# talkbit.net
KiCad netlist of a schematic drawn in EAGLE
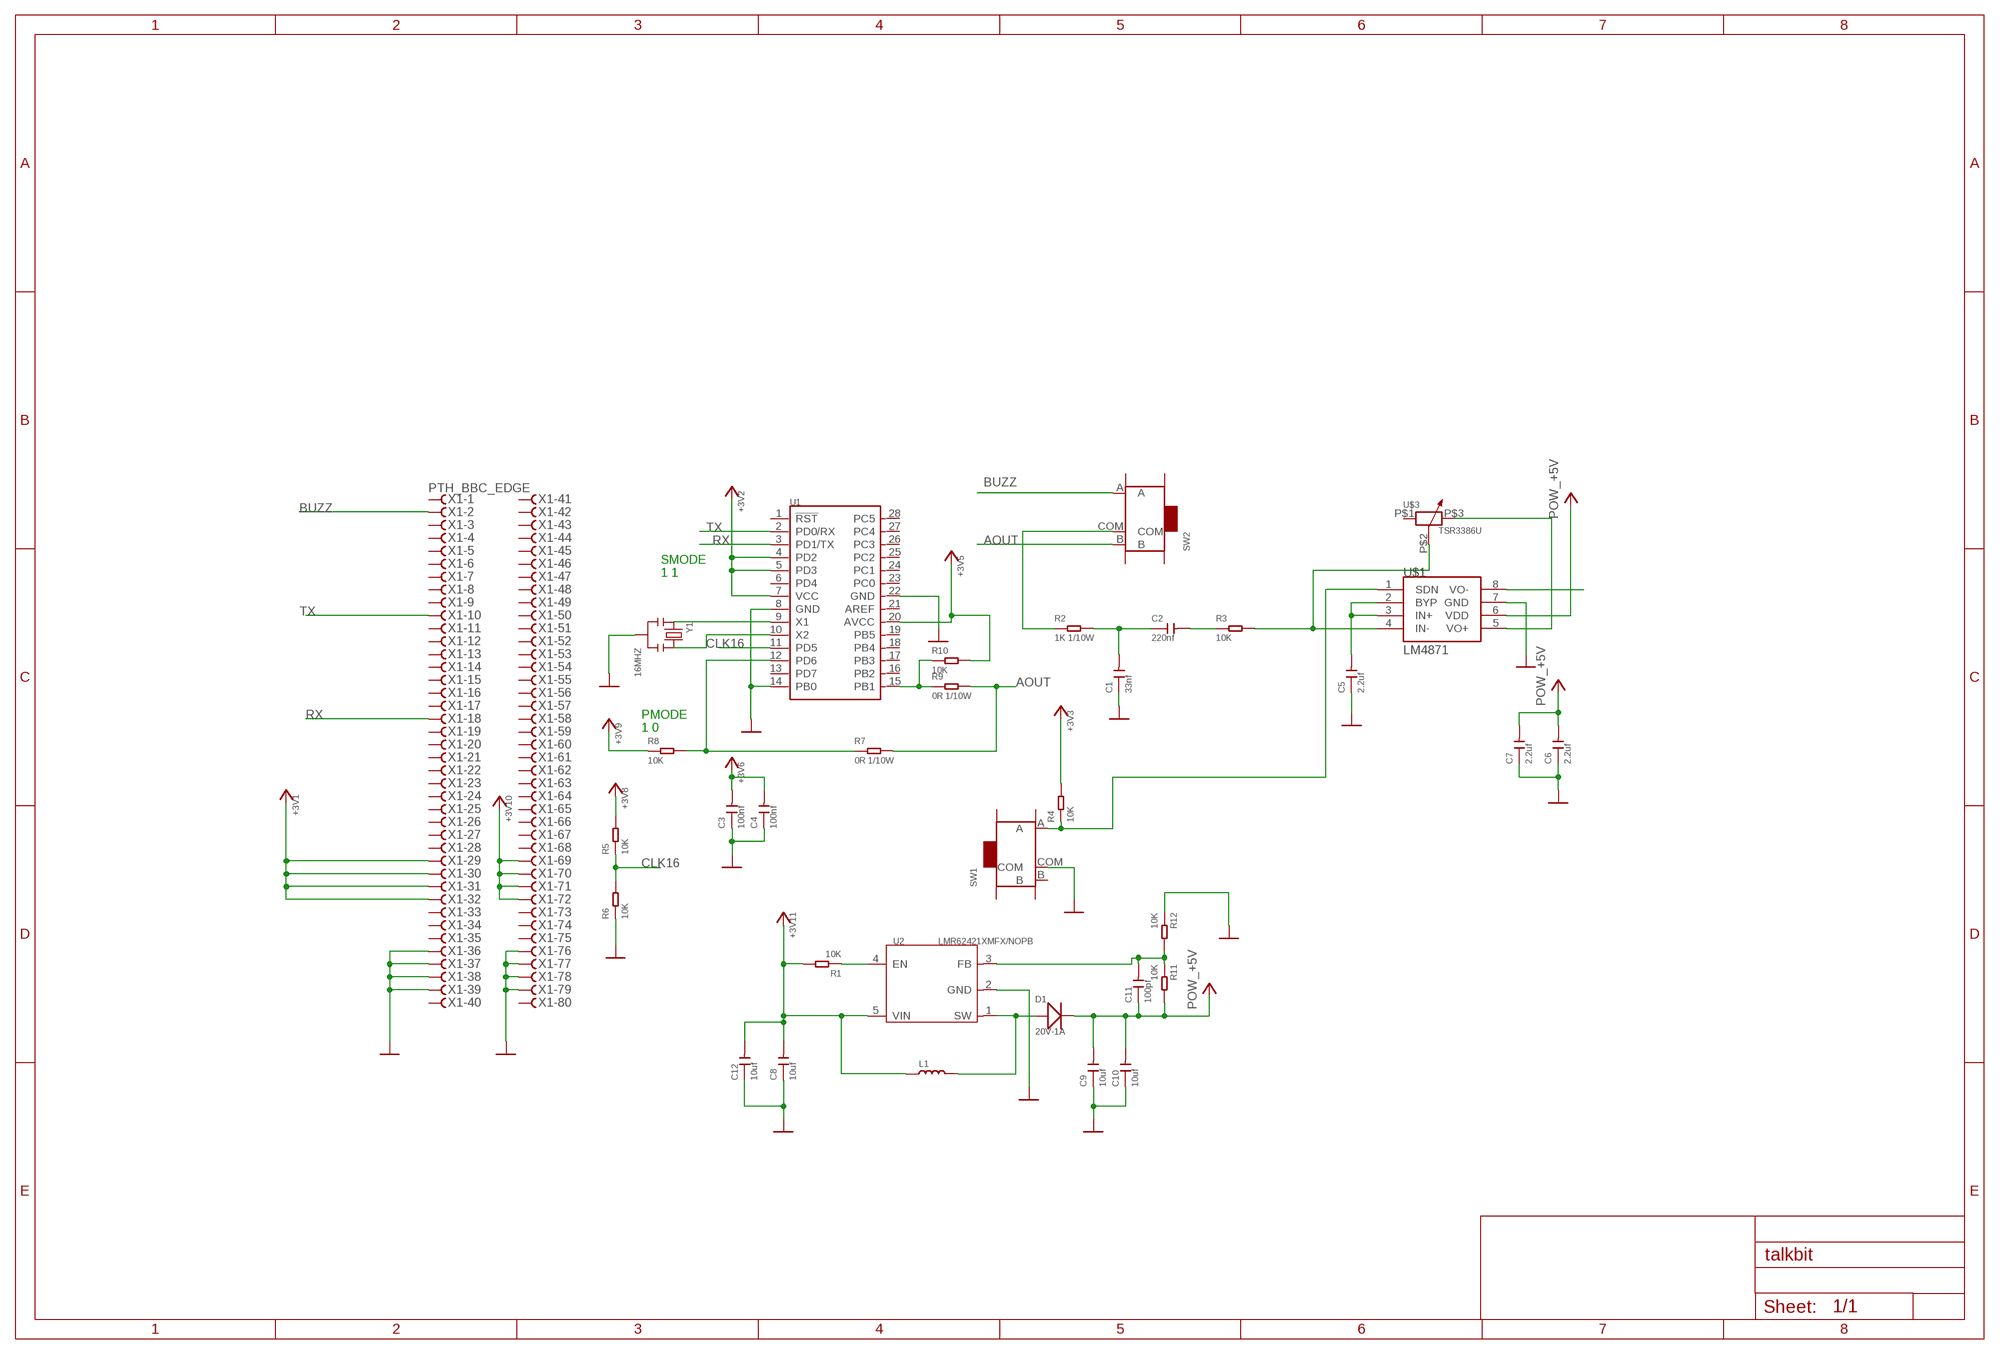
[diagram p0: schematic, sheet 1]

(export (version "E")
  (design (tool "Eeschema 10.0.6"))
  (components
    (comp (ref "C1")
      (value "33nf")
      (footprint "eagle-import:C0603")
      (fields (field (name "MPN") "CC0603KRX7R9BB333"))
      (libsource (lib "eagle-import") (part "CERAMIC-33NF-50V-10%-X7R(0603)"))
    )
    (comp (ref "C2")
      (value "220nf")
      (footprint "eagle-import:C0603")
      (fields (field (name "MPN") "CC0603KRX7R8BB224"))
      (libsource (lib "eagle-import") (part "CERAMIC-220NF-25V-10%-X7R(0603)"))
    )
    (comp (ref "C3")
      (value "100nf")
      (footprint "eagle-import:C0603")
      (fields (field (name "MPN") "CC0603KRX7R9BB104"))
      (libsource (lib "eagle-import") (part "CERAMIC-100NF-50V-10%-X7R(0603)"))
    )
    (comp (ref "C4")
      (value "100nf")
      (footprint "eagle-import:C0603")
      (fields (field (name "MPN") "CC0603KRX7R9BB104"))
      (libsource (lib "eagle-import") (part "CERAMIC-100NF-50V-10%-X7R(0603)"))
    )
    (comp (ref "C5")
      (value "2.2uf")
      (footprint "eagle-import:C0603")
      (fields (field (name "MPN") "CC0603KRX7R6BB225"))
      (libsource (lib "eagle-import") (part "CERAMIC-2.2UF-10V-10%-X7R(0603)"))
    )
    (comp (ref "C6")
      (value "2.2uf")
      (footprint "eagle-import:C0603")
      (fields (field (name "MPN") "CC0603KRX7R6BB225"))
      (libsource (lib "eagle-import") (part "CERAMIC-2.2UF-10V-10%-X7R(0603)"))
    )
    (comp (ref "C7")
      (value "2.2uf")
      (footprint "eagle-import:C0603")
      (fields (field (name "MPN") "CC0603KRX7R6BB225"))
      (libsource (lib "eagle-import") (part "CERAMIC-2.2UF-10V-10%-X7R(0603)"))
    )
    (comp (ref "C8")
      (value "10uf")
      (footprint "eagle-import:C0603")
      (fields (field (name "MPN") "CC0603KRX5R6BB106"))
      (libsource (lib "eagle-import") (part "CERAMIC-10UF-10V-10%-X5R(0603)"))
    )
    (comp (ref "C9")
      (value "10uf")
      (footprint "eagle-import:C0603")
      (fields (field (name "MPN") "CC0603KRX5R6BB106"))
      (libsource (lib "eagle-import") (part "CERAMIC-10UF-10V-10%-X5R(0603)"))
    )
    (comp (ref "C10")
      (value "10uf")
      (footprint "eagle-import:C0603")
      (fields (field (name "MPN") "CC0603KRX5R6BB106"))
      (libsource (lib "eagle-import") (part "CERAMIC-10UF-10V-10%-X5R(0603)"))
    )
    (comp (ref "C11")
      (value "100pf")
      (footprint "eagle-import:C0603")
      (fields (field (name "MPN") "CC0603JRNPO9BN101"))
      (libsource (lib "eagle-import") (part "CERAMIC-100PF-50V-5%-NPO(0603)"))
    )
    (comp (ref "C12")
      (value "10uf")
      (footprint "eagle-import:C0603")
      (fields (field (name "MPN") "CC0603KRX5R6BB106"))
      (libsource (lib "eagle-import") (part "CERAMIC-10UF-10V-10%-X5R(0603)"))
    )
    (comp (ref "D1")
      (value "20V-1A")
      (footprint "eagle-import:SOD-123")
      (fields (field (name "MPN") "B5819W"))
      (libsource (lib "eagle-import") (part "SMD-DIODE-SCHOTTKY-20V-1A(SOD-123)"))
    )
    (comp (ref "L1")
      (value "SMD-INDUCTOR-10UH-20%-2.35A(2P-5X5X4MM)")
      (footprint "eagle-import:L5040S")
      (libsource (lib "eagle-import") (part "SMD-INDUCTOR-10UH-20%-2.35A(2P-5X5X4MM)"))
    )
    (comp (ref "R1")
      (value "10K")
      (footprint "eagle-import:R0603")
      (fields (field (name "MPN") "RC0603FR-0710KL"))
      (libsource (lib "eagle-import") (part "SMD-RES-10K-1%-1/10W(0603)"))
    )
    (comp (ref "R2")
      (value "1K 1/10W")
      (footprint "eagle-import:R0603")
      (fields (field (name "MPN") "RC0603JR-071KL"))
      (libsource (lib "eagle-import") (part "SMD-RES-1K-5%-1/10W(0603)"))
    )
    (comp (ref "R3")
      (value "10K")
      (footprint "eagle-import:R0603")
      (fields (field (name "MPN") "RC0603FR-0710KL"))
      (libsource (lib "eagle-import") (part "SMD-RES-10K-1%-1/10W(0603)"))
    )
    (comp (ref "R4")
      (value "10K")
      (footprint "eagle-import:R0603")
      (fields (field (name "MPN") "RC0603FR-0710KL"))
      (libsource (lib "eagle-import") (part "SMD-RES-10K-1%-1/10W(0603)"))
    )
    (comp (ref "R5")
      (value "10K")
      (footprint "eagle-import:R0603")
      (fields (field (name "MPN") "RC0603FR-0710KL"))
      (libsource (lib "eagle-import") (part "SMD-RES-10K-1%-1/10W(0603)"))
    )
    (comp (ref "R6")
      (value "10K")
      (footprint "eagle-import:R0603")
      (fields (field (name "MPN") "RC0603FR-0710KL"))
      (libsource (lib "eagle-import") (part "SMD-RES-10K-1%-1/10W(0603)"))
    )
    (comp (ref "R7")
      (value "0R 1/10W")
      (footprint "eagle-import:R0603")
      (fields (field (name "MPN") "AC0603FR-070RL"))
      (libsource (lib "eagle-import") (part "SMD-RES-0R-1%-1/10W(0603)"))
    )
    (comp (ref "R8")
      (value "10K")
      (footprint "eagle-import:R0603")
      (fields (field (name "MPN") "RC0603FR-0710KL"))
      (libsource (lib "eagle-import") (part "SMD-RES-10K-1%-1/10W(0603)"))
    )
    (comp (ref "R9")
      (value "0R 1/10W")
      (footprint "eagle-import:R0603")
      (fields (field (name "MPN") "AC0603FR-070RL"))
      (libsource (lib "eagle-import") (part "SMD-RES-0R-1%-1/10W(0603)"))
    )
    (comp (ref "R10")
      (value "10K")
      (footprint "eagle-import:R0603")
      (fields (field (name "MPN") "RC0603FR-0710KL"))
      (libsource (lib "eagle-import") (part "SMD-RES-10K-1%-1/10W(0603)"))
    )
    (comp (ref "R11")
      (value "10K")
      (footprint "eagle-import:R0603")
      (fields (field (name "MPN") "RC0603FR-0710KL"))
      (libsource (lib "eagle-import") (part "SMD-RES-10K-1%-1/10W(0603)"))
    )
    (comp (ref "R12")
      (value "10K")
      (footprint "eagle-import:R0603")
      (fields (field (name "MPN") "RC0603FR-0710KL"))
      (libsource (lib "eagle-import") (part "SMD-RES-10K-1%-1/10W(0603)"))
    )
    (comp (ref "SW1")
      (value "SMD-TOGGLE-SWITCH-ON-ON(3+4P-6.7X2.7MM)")
      (footprint "eagle-import:SW7-SMD-L6.7X2.7X3.2MM")
      (libsource (lib "eagle-import") (part "SMD-TOGGLE-SWITCH-ON-ON(3+4P-6.7X2.7MM)"))
    )
    (comp (ref "SW2")
      (value "SMD-TOGGLE-SWITCH-ON-ON(3+4P-6.7X2.7MM)")
      (footprint "eagle-import:SW7-SMD-L6.7X2.7X3.2MM")
      (libsource (lib "eagle-import") (part "SMD-TOGGLE-SWITCH-ON-ON(3+4P-6.7X2.7MM)"))
    )
    (comp (ref "U$1")
      (value "LM4871")
      (footprint "eagle-import:SOIC8")
      (libsource (lib "eagle-import") (part "TPA701"))
    )
    (comp (ref "U$3")
      (value "TSR3386U")
      (footprint "eagle-import:DIP3")
      (libsource (lib "eagle-import") (part "TSR3386U"))
    )
    (comp (ref "U1")
      (value "MCU-ATMEGA328P-PU(DIP28)")
      (footprint "eagle-import:DIP28-2.54-35.6X13.5MM")
      (fields (field (name "MPN") "ATMEGA328P-PU"))
      (libsource (lib "eagle-import") (part "MCU-ATMEGA328P-PU(DIP28)"))
    )
    (comp (ref "U2")
      (value "LMR62421XMFX/NOPB")
      (footprint "eagle-import:SOT-23-5")
      (fields (field (name "MPN") "LMR10510YMFE/NOPB"))
      (libsource (lib "eagle-import") (part "PMIC-LMR10510YMFE/NOPB(SOT23-5)"))
    )
    (comp (ref "X1")
      (value "PTH_BBC_EDGE")
      (footprint "eagle-import:PTH_BBC_EDGE")
      (libsource (lib "eagle-import") (part "PTH_BBC_EDGE"))
    )
    (comp (ref "Y1")
      (value "16MHZ")
      (footprint "eagle-import:X3-SMD-3.6X1.3X0.8MM")
      (fields (field (name "MPN") "CSTCE16M0V53-R0"))
      (libsource (lib "eagle-import") (part "SMD-RESONATOR-16MHZ-15PF-0.5%-40R(3P-3.2X1.3MM)"))
    )
  )
  (nets
    (net (code "1") (name "/AOUT") (class "Default")
      (node (ref "R7") (pin "2") (pinfunction "2_2") (pintype "passive"))
      (node (ref "R9") (pin "2") (pinfunction "2_2") (pintype "passive"))
      (node (ref "SW2") (pin "B") (pinfunction "B_B") (pintype "bidirectional"))
    )
    (net (code "2") (name "/BUZZ") (class "Default")
      (node (ref "SW2") (pin "A") (pinfunction "A_A") (pintype "bidirectional"))
      (node (ref "X1") (pin "2") (pinfunction "F_2") (pintype "passive"))
    )
    (net (code "3") (name "/CLK16") (class "Default")
      (node (ref "R5") (pin "1") (pinfunction "1_1") (pintype "passive"))
      (node (ref "R6") (pin "2") (pinfunction "2_2") (pintype "passive"))
      (node (ref "U1") (pin "11") (pinfunction "PD5_11") (pintype "bidirectional"))
    )
    (net (code "4") (name "/RX") (class "Default")
      (node (ref "U1") (pin "3") (pinfunction "PD1/TX_3") (pintype "bidirectional"))
      (node (ref "X1") (pin "18") (pinfunction "F_18") (pintype "passive"))
    )
    (net (code "5") (name "/TX") (class "Default")
      (node (ref "U1") (pin "2") (pinfunction "PD0/RX_2") (pintype "bidirectional"))
      (node (ref "X1") (pin "10") (pinfunction "F_10") (pintype "passive"))
    )
    (net (code "6") (name "Net-(C1-Pad2)") (class "Default")
      (node (ref "C1") (pin "2") (pinfunction "2_2") (pintype "passive"))
      (node (ref "C2") (pin "1") (pinfunction "1_1") (pintype "passive"))
      (node (ref "R2") (pin "2") (pinfunction "2_2") (pintype "passive"))
    )
    (net (code "7") (name "Net-(C2-Pad2)") (class "Default")
      (node (ref "C2") (pin "2") (pinfunction "2_2") (pintype "passive"))
      (node (ref "R3") (pin "1") (pinfunction "1_1") (pintype "passive"))
    )
    (net (code "8") (name "Net-(R2-Pad1)") (class "Default")
      (node (ref "R2") (pin "1") (pinfunction "1_1") (pintype "passive"))
      (node (ref "SW2") (pin "COM") (pinfunction "COM_COM") (pintype "bidirectional"))
    )
    (net (code "9") (name "Net-(U$1-BYP)") (class "Default")
      (node (ref "C5") (pin "2") (pinfunction "2_2") (pintype "passive"))
      (node (ref "U$1") (pin "2") (pinfunction "BYP_2") (pintype "bidirectional"))
      (node (ref "U$1") (pin "3") (pinfunction "IN+_3") (pintype "bidirectional"))
    )
    (net (code "10") (name "Net-(U$1-IN-)") (class "Default")
      (node (ref "R3") (pin "2") (pinfunction "2_2") (pintype "passive"))
      (node (ref "U$1") (pin "4") (pinfunction "IN-_4") (pintype "bidirectional"))
      (node (ref "U$3") (pin "P$2") (pinfunction "3_P$2") (pintype "passive"))
    )
    (net (code "11") (name "Net-(U$1-SDN)") (class "Default")
      (node (ref "R4") (pin "1") (pinfunction "1_1") (pintype "passive"))
      (node (ref "SW1") (pin "A") (pinfunction "A_A") (pintype "bidirectional"))
      (node (ref "U$1") (pin "1") (pinfunction "SDN_1") (pintype "bidirectional"))
    )
    (net (code "12") (name "Net-(U$1-VO+)") (class "Default")
      (node (ref "U$1") (pin "5") (pinfunction "VO+_5") (pintype "bidirectional"))
      (node (ref "U$3") (pin "P$3") (pinfunction "2_P$3") (pintype "passive"))
    )
    (net (code "13") (name "Net-(U1-PB1)") (class "Default")
      (node (ref "R10") (pin "1") (pinfunction "1_1") (pintype "passive"))
      (node (ref "R9") (pin "1") (pinfunction "1_1") (pintype "passive"))
      (node (ref "U1") (pin "15") (pinfunction "PB1_15") (pintype "bidirectional"))
    )
    (net (code "14") (name "Net-(U1-PD6)") (class "Default")
      (node (ref "R7") (pin "1") (pinfunction "1_1") (pintype "passive"))
      (node (ref "R8") (pin "2") (pinfunction "2_2") (pintype "passive"))
      (node (ref "U1") (pin "12") (pinfunction "PD6_12") (pintype "bidirectional"))
    )
    (net (code "15") (name "Net-(U1-X1)") (class "Default")
      (node (ref "U1") (pin "9") (pinfunction "X1_9") (pintype "bidirectional"))
      (node (ref "Y1") (pin "1") (pinfunction "1_1") (pintype "passive"))
    )
    (net (code "16") (name "Net-(U1-X2)") (class "Default")
      (node (ref "U1") (pin "10") (pinfunction "X2_10") (pintype "bidirectional"))
      (node (ref "Y1") (pin "3") (pinfunction "3_3") (pintype "passive"))
    )
    (net (code "17") (name "Net-(U2-EN)") (class "Default")
      (node (ref "R1") (pin "1") (pinfunction "1_1") (pintype "passive"))
      (node (ref "U2") (pin "4") (pinfunction "EN_4") (pintype "bidirectional"))
    )
    (net (code "18") (name "Net-(U2-FB)") (class "Default")
      (node (ref "C11") (pin "2") (pinfunction "2_2") (pintype "passive"))
      (node (ref "R11") (pin "1") (pinfunction "1_1") (pintype "passive"))
      (node (ref "R12") (pin "2") (pinfunction "2_2") (pintype "passive"))
      (node (ref "U2") (pin "3") (pinfunction "FB_3") (pintype "bidirectional"))
    )
    (net (code "19") (name "Net-(U2-SW)") (class "Default")
      (node (ref "D1") (pin "+") (pinfunction "+_+") (pintype "passive"))
      (node (ref "L1") (pin "2") (pinfunction "2_2") (pintype "passive"))
      (node (ref "U2") (pin "1") (pinfunction "SW_1") (pintype "bidirectional"))
    )
    (net (code "20") (name "POW_+3V3") (class "Default")
      (node (ref "C12") (pin "2") (pinfunction "2_2") (pintype "passive"))
      (node (ref "C3") (pin "2") (pinfunction "2_2") (pintype "passive"))
      (node (ref "C4") (pin "2") (pinfunction "2_2") (pintype "passive"))
      (node (ref "C8") (pin "2") (pinfunction "2_2") (pintype "passive"))
      (node (ref "L1") (pin "1") (pinfunction "1_1") (pintype "passive"))
      (node (ref "R1") (pin "2") (pinfunction "2_2") (pintype "passive"))
      (node (ref "R10") (pin "2") (pinfunction "2_2") (pintype "passive"))
      (node (ref "R4") (pin "2") (pinfunction "2_2") (pintype "passive"))
      (node (ref "R5") (pin "2") (pinfunction "2_2") (pintype "passive"))
      (node (ref "R8") (pin "1") (pinfunction "1_1") (pintype "passive"))
      (node (ref "U1") (pin "20") (pinfunction "AVCC_20") (pintype "bidirectional"))
      (node (ref "U1") (pin "4") (pinfunction "PD2_4") (pintype "bidirectional"))
      (node (ref "U1") (pin "5") (pinfunction "PD3_5") (pintype "bidirectional"))
      (node (ref "U1") (pin "7") (pinfunction "VCC_7") (pintype "bidirectional"))
      (node (ref "U2") (pin "5") (pinfunction "VIN_5") (pintype "bidirectional"))
      (node (ref "X1") (pin "29") (pinfunction "F_29") (pintype "passive"))
      (node (ref "X1") (pin "30") (pinfunction "F_30") (pintype "passive"))
      (node (ref "X1") (pin "31") (pinfunction "F_31") (pintype "passive"))
      (node (ref "X1") (pin "32") (pinfunction "F_32") (pintype "passive"))
      (node (ref "X1") (pin "69") (pinfunction "F_69") (pintype "passive"))
      (node (ref "X1") (pin "70") (pinfunction "F_70") (pintype "passive"))
      (node (ref "X1") (pin "71") (pinfunction "F_71") (pintype "passive"))
      (node (ref "X1") (pin "72") (pinfunction "F_72") (pintype "passive"))
    )
    (net (code "21") (name "POW_+5V") (class "Default")
      (node (ref "C10") (pin "2") (pinfunction "2_2") (pintype "passive"))
      (node (ref "C11") (pin "1") (pinfunction "1_1") (pintype "passive"))
      (node (ref "C6") (pin "2") (pinfunction "2_2") (pintype "passive"))
      (node (ref "C7") (pin "2") (pinfunction "2_2") (pintype "passive"))
      (node (ref "C9") (pin "2") (pinfunction "2_2") (pintype "passive"))
      (node (ref "D1") (pin "-") (pinfunction "-_-") (pintype "passive"))
      (node (ref "R11") (pin "2") (pinfunction "2_2") (pintype "passive"))
      (node (ref "U$1") (pin "6") (pinfunction "VDD_6") (pintype "bidirectional"))
    )
    (net (code "22") (name "POW_GND") (class "Default")
      (node (ref "C1") (pin "1") (pinfunction "1_1") (pintype "passive"))
      (node (ref "C10") (pin "1") (pinfunction "1_1") (pintype "passive"))
      (node (ref "C12") (pin "1") (pinfunction "1_1") (pintype "passive"))
      (node (ref "C3") (pin "1") (pinfunction "1_1") (pintype "passive"))
      (node (ref "C4") (pin "1") (pinfunction "1_1") (pintype "passive"))
      (node (ref "C5") (pin "1") (pinfunction "1_1") (pintype "passive"))
      (node (ref "C6") (pin "1") (pinfunction "1_1") (pintype "passive"))
      (node (ref "C7") (pin "1") (pinfunction "1_1") (pintype "passive"))
      (node (ref "C8") (pin "1") (pinfunction "1_1") (pintype "passive"))
      (node (ref "C9") (pin "1") (pinfunction "1_1") (pintype "passive"))
      (node (ref "R12") (pin "1") (pinfunction "1_1") (pintype "passive"))
      (node (ref "R6") (pin "1") (pinfunction "1_1") (pintype "passive"))
      (node (ref "SW1") (pin "COM") (pinfunction "COM_COM") (pintype "bidirectional"))
      (node (ref "U$1") (pin "7") (pinfunction "GND_7") (pintype "bidirectional"))
      (node (ref "U1") (pin "14") (pinfunction "PB0_14") (pintype "bidirectional"))
      (node (ref "U1") (pin "22") (pinfunction "GND_22") (pintype "bidirectional"))
      (node (ref "U1") (pin "8") (pinfunction "GND_8") (pintype "bidirectional"))
      (node (ref "U2") (pin "2") (pinfunction "GND_2") (pintype "bidirectional"))
      (node (ref "X1") (pin "36") (pinfunction "F_36") (pintype "passive"))
      (node (ref "X1") (pin "37") (pinfunction "F_37") (pintype "passive"))
      (node (ref "X1") (pin "38") (pinfunction "F_38") (pintype "passive"))
      (node (ref "X1") (pin "39") (pinfunction "F_39") (pintype "passive"))
      (node (ref "X1") (pin "76") (pinfunction "F_76") (pintype "passive"))
      (node (ref "X1") (pin "77") (pinfunction "F_77") (pintype "passive"))
      (node (ref "X1") (pin "78") (pinfunction "F_78") (pintype "passive"))
      (node (ref "X1") (pin "79") (pinfunction "F_79") (pintype "passive"))
      (node (ref "Y1") (pin "2") (pinfunction "2_2") (pintype "passive"))
    )
    (net (code "23") (name "unconnected-(SW1-PadB)") (class "Default")
      (node (ref "SW1") (pin "B") (pinfunction "B_B") (pintype "bidirectional"))
    )
    (net (code "24") (name "unconnected-(SW1-PadSS1)") (class "Default")
      (node (ref "SW1") (pin "SS1") (pinfunction "SS1_SS1") (pintype "bidirectional"))
    )
    (net (code "25") (name "unconnected-(SW1-PadSS2)") (class "Default")
      (node (ref "SW1") (pin "SS2") (pinfunction "SS2_SS2") (pintype "bidirectional"))
    )
    (net (code "26") (name "unconnected-(SW1-PadSS3)") (class "Default")
      (node (ref "SW1") (pin "SS3") (pinfunction "SS3_SS3") (pintype "bidirectional"))
    )
    (net (code "27") (name "unconnected-(SW1-PadSS4)") (class "Default")
      (node (ref "SW1") (pin "SS4") (pinfunction "SS4_SS4") (pintype "bidirectional"))
    )
    (net (code "28") (name "unconnected-(SW2-PadSS1)") (class "Default")
      (node (ref "SW2") (pin "SS1") (pinfunction "SS1_SS1") (pintype "bidirectional"))
    )
    (net (code "29") (name "unconnected-(SW2-PadSS2)") (class "Default")
      (node (ref "SW2") (pin "SS2") (pinfunction "SS2_SS2") (pintype "bidirectional"))
    )
    (net (code "30") (name "unconnected-(SW2-PadSS3)") (class "Default")
      (node (ref "SW2") (pin "SS3") (pinfunction "SS3_SS3") (pintype "bidirectional"))
    )
    (net (code "31") (name "unconnected-(SW2-PadSS4)") (class "Default")
      (node (ref "SW2") (pin "SS4") (pinfunction "SS4_SS4") (pintype "bidirectional"))
    )
    (net (code "32") (name "unconnected-(U$1-VO--Pad8)") (class "Default")
      (node (ref "U$1") (pin "8") (pinfunction "VO-_8") (pintype "bidirectional"))
    )
    (net (code "33") (name "unconnected-(U$3-1-PadP$1)") (class "Default")
      (node (ref "U$3") (pin "P$1") (pinfunction "1_P$1") (pintype "passive"))
    )
    (net (code "34") (name "unconnected-(U1-AREF-Pad21)") (class "Default")
      (node (ref "U1") (pin "21") (pinfunction "AREF_21") (pintype "bidirectional"))
    )
    (net (code "35") (name "unconnected-(U1-PB2-Pad16)") (class "Default")
      (node (ref "U1") (pin "16") (pinfunction "PB2_16") (pintype "bidirectional"))
    )
    (net (code "36") (name "unconnected-(U1-PB3-Pad17)") (class "Default")
      (node (ref "U1") (pin "17") (pinfunction "PB3_17") (pintype "bidirectional"))
    )
    (net (code "37") (name "unconnected-(U1-PB4-Pad18)") (class "Default")
      (node (ref "U1") (pin "18") (pinfunction "PB4_18") (pintype "bidirectional"))
    )
    (net (code "38") (name "unconnected-(U1-PB5-Pad19)") (class "Default")
      (node (ref "U1") (pin "19") (pinfunction "PB5_19") (pintype "bidirectional"))
    )
    (net (code "39") (name "unconnected-(U1-PC0-Pad23)") (class "Default")
      (node (ref "U1") (pin "23") (pinfunction "PC0_23") (pintype "bidirectional"))
    )
    (net (code "40") (name "unconnected-(U1-PC1-Pad24)") (class "Default")
      (node (ref "U1") (pin "24") (pinfunction "PC1_24") (pintype "bidirectional"))
    )
    (net (code "41") (name "unconnected-(U1-PC2-Pad25)") (class "Default")
      (node (ref "U1") (pin "25") (pinfunction "PC2_25") (pintype "bidirectional"))
    )
    (net (code "42") (name "unconnected-(U1-PC3-Pad26)") (class "Default")
      (node (ref "U1") (pin "26") (pinfunction "PC3_26") (pintype "bidirectional"))
    )
    (net (code "43") (name "unconnected-(U1-PC4-Pad27)") (class "Default")
      (node (ref "U1") (pin "27") (pinfunction "PC4_27") (pintype "bidirectional"))
    )
    (net (code "44") (name "unconnected-(U1-PC5-Pad28)") (class "Default")
      (node (ref "U1") (pin "28") (pinfunction "PC5_28") (pintype "bidirectional"))
    )
    (net (code "45") (name "unconnected-(U1-PD4-Pad6)") (class "Default")
      (node (ref "U1") (pin "6") (pinfunction "PD4_6") (pintype "bidirectional"))
    )
    (net (code "46") (name "unconnected-(U1-PD7-Pad13)") (class "Default")
      (node (ref "U1") (pin "13") (pinfunction "PD7_13") (pintype "bidirectional"))
    )
    (net (code "47") (name "unconnected-(U1-~{RST}-Pad1)") (class "Default")
      (node (ref "U1") (pin "1") (pinfunction "~{RST}_1") (pintype "bidirectional"))
    )
    (net (code "48") (name "unconnected-(X1A-F-Pad1)") (class "Default")
      (node (ref "X1") (pin "1") (pinfunction "F_1") (pintype "passive"))
    )
    (net (code "49") (name "unconnected-(X1AA-F-Pad33)") (class "Default")
      (node (ref "X1") (pin "33") (pinfunction "F_33") (pintype "passive"))
    )
    (net (code "50") (name "unconnected-(X1AB-F-Pad34)") (class "Default")
      (node (ref "X1") (pin "34") (pinfunction "F_34") (pintype "passive"))
    )
    (net (code "51") (name "unconnected-(X1AC-F-Pad35)") (class "Default")
      (node (ref "X1") (pin "35") (pinfunction "F_35") (pintype "passive"))
    )
    (net (code "52") (name "unconnected-(X1AH-F-Pad4)") (class "Default")
      (node (ref "X1") (pin "4") (pinfunction "F_4") (pintype "passive"))
    )
    (net (code "53") (name "unconnected-(X1AI-F-Pad40)") (class "Default")
      (node (ref "X1") (pin "40") (pinfunction "F_40") (pintype "passive"))
    )
    (net (code "54") (name "unconnected-(X1AJ-F-Pad41)") (class "Default")
      (node (ref "X1") (pin "41") (pinfunction "F_41") (pintype "passive"))
    )
    (net (code "55") (name "unconnected-(X1AK-F-Pad42)") (class "Default")
      (node (ref "X1") (pin "42") (pinfunction "F_42") (pintype "passive"))
    )
    (net (code "56") (name "unconnected-(X1AL-F-Pad43)") (class "Default")
      (node (ref "X1") (pin "43") (pinfunction "F_43") (pintype "passive"))
    )
    (net (code "57") (name "unconnected-(X1AM-F-Pad44)") (class "Default")
      (node (ref "X1") (pin "44") (pinfunction "F_44") (pintype "passive"))
    )
    (net (code "58") (name "unconnected-(X1AN-F-Pad45)") (class "Default")
      (node (ref "X1") (pin "45") (pinfunction "F_45") (pintype "passive"))
    )
    (net (code "59") (name "unconnected-(X1AO-F-Pad46)") (class "Default")
      (node (ref "X1") (pin "46") (pinfunction "F_46") (pintype "passive"))
    )
    (net (code "60") (name "unconnected-(X1AP-F-Pad47)") (class "Default")
      (node (ref "X1") (pin "47") (pinfunction "F_47") (pintype "passive"))
    )
    (net (code "61") (name "unconnected-(X1AQ-F-Pad48)") (class "Default")
      (node (ref "X1") (pin "48") (pinfunction "F_48") (pintype "passive"))
    )
    (net (code "62") (name "unconnected-(X1AR-F-Pad49)") (class "Default")
      (node (ref "X1") (pin "49") (pinfunction "F_49") (pintype "passive"))
    )
    (net (code "63") (name "unconnected-(X1AS-F-Pad5)") (class "Default")
      (node (ref "X1") (pin "5") (pinfunction "F_5") (pintype "passive"))
    )
    (net (code "64") (name "unconnected-(X1AT-F-Pad50)") (class "Default")
      (node (ref "X1") (pin "50") (pinfunction "F_50") (pintype "passive"))
    )
    (net (code "65") (name "unconnected-(X1AU-F-Pad51)") (class "Default")
      (node (ref "X1") (pin "51") (pinfunction "F_51") (pintype "passive"))
    )
    (net (code "66") (name "unconnected-(X1AV-F-Pad52)") (class "Default")
      (node (ref "X1") (pin "52") (pinfunction "F_52") (pintype "passive"))
    )
    (net (code "67") (name "unconnected-(X1AW-F-Pad53)") (class "Default")
      (node (ref "X1") (pin "53") (pinfunction "F_53") (pintype "passive"))
    )
    (net (code "68") (name "unconnected-(X1AX-F-Pad54)") (class "Default")
      (node (ref "X1") (pin "54") (pinfunction "F_54") (pintype "passive"))
    )
    (net (code "69") (name "unconnected-(X1AY-F-Pad55)") (class "Default")
      (node (ref "X1") (pin "55") (pinfunction "F_55") (pintype "passive"))
    )
    (net (code "70") (name "unconnected-(X1AZ-F-Pad56)") (class "Default")
      (node (ref "X1") (pin "56") (pinfunction "F_56") (pintype "passive"))
    )
    (net (code "71") (name "unconnected-(X1BA-F-Pad57)") (class "Default")
      (node (ref "X1") (pin "57") (pinfunction "F_57") (pintype "passive"))
    )
    (net (code "72") (name "unconnected-(X1BB-F-Pad58)") (class "Default")
      (node (ref "X1") (pin "58") (pinfunction "F_58") (pintype "passive"))
    )
    (net (code "73") (name "unconnected-(X1BC-F-Pad59)") (class "Default")
      (node (ref "X1") (pin "59") (pinfunction "F_59") (pintype "passive"))
    )
    (net (code "74") (name "unconnected-(X1BD-F-Pad6)") (class "Default")
      (node (ref "X1") (pin "6") (pinfunction "F_6") (pintype "passive"))
    )
    (net (code "75") (name "unconnected-(X1BE-F-Pad60)") (class "Default")
      (node (ref "X1") (pin "60") (pinfunction "F_60") (pintype "passive"))
    )
    (net (code "76") (name "unconnected-(X1BF-F-Pad61)") (class "Default")
      (node (ref "X1") (pin "61") (pinfunction "F_61") (pintype "passive"))
    )
    (net (code "77") (name "unconnected-(X1BG-F-Pad62)") (class "Default")
      (node (ref "X1") (pin "62") (pinfunction "F_62") (pintype "passive"))
    )
    (net (code "78") (name "unconnected-(X1BH-F-Pad63)") (class "Default")
      (node (ref "X1") (pin "63") (pinfunction "F_63") (pintype "passive"))
    )
    (net (code "79") (name "unconnected-(X1BI-F-Pad64)") (class "Default")
      (node (ref "X1") (pin "64") (pinfunction "F_64") (pintype "passive"))
    )
    (net (code "80") (name "unconnected-(X1BJ-F-Pad65)") (class "Default")
      (node (ref "X1") (pin "65") (pinfunction "F_65") (pintype "passive"))
    )
    (net (code "81") (name "unconnected-(X1BK-F-Pad66)") (class "Default")
      (node (ref "X1") (pin "66") (pinfunction "F_66") (pintype "passive"))
    )
    (net (code "82") (name "unconnected-(X1BL-F-Pad67)") (class "Default")
      (node (ref "X1") (pin "67") (pinfunction "F_67") (pintype "passive"))
    )
    (net (code "83") (name "unconnected-(X1BM-F-Pad68)") (class "Default")
      (node (ref "X1") (pin "68") (pinfunction "F_68") (pintype "passive"))
    )
    (net (code "84") (name "unconnected-(X1BO-F-Pad7)") (class "Default")
      (node (ref "X1") (pin "7") (pinfunction "F_7") (pintype "passive"))
    )
    (net (code "85") (name "unconnected-(X1BS-F-Pad73)") (class "Default")
      (node (ref "X1") (pin "73") (pinfunction "F_73") (pintype "passive"))
    )
    (net (code "86") (name "unconnected-(X1BT-F-Pad74)") (class "Default")
      (node (ref "X1") (pin "74") (pinfunction "F_74") (pintype "passive"))
    )
    (net (code "87") (name "unconnected-(X1BU-F-Pad75)") (class "Default")
      (node (ref "X1") (pin "75") (pinfunction "F_75") (pintype "passive"))
    )
    (net (code "88") (name "unconnected-(X1BZ-F-Pad8)") (class "Default")
      (node (ref "X1") (pin "8") (pinfunction "F_8") (pintype "passive"))
    )
    (net (code "89") (name "unconnected-(X1C-F-Pad11)") (class "Default")
      (node (ref "X1") (pin "11") (pinfunction "F_11") (pintype "passive"))
    )
    (net (code "90") (name "unconnected-(X1CA-F-Pad80)") (class "Default")
      (node (ref "X1") (pin "80") (pinfunction "F_80") (pintype "passive"))
    )
    (net (code "91") (name "unconnected-(X1CB-F-Pad9)") (class "Default")
      (node (ref "X1") (pin "9") (pinfunction "F_9") (pintype "passive"))
    )
    (net (code "92") (name "unconnected-(X1D-F-Pad12)") (class "Default")
      (node (ref "X1") (pin "12") (pinfunction "F_12") (pintype "passive"))
    )
    (net (code "93") (name "unconnected-(X1E-F-Pad13)") (class "Default")
      (node (ref "X1") (pin "13") (pinfunction "F_13") (pintype "passive"))
    )
    (net (code "94") (name "unconnected-(X1F-F-Pad14)") (class "Default")
      (node (ref "X1") (pin "14") (pinfunction "F_14") (pintype "passive"))
    )
    (net (code "95") (name "unconnected-(X1G-F-Pad15)") (class "Default")
      (node (ref "X1") (pin "15") (pinfunction "F_15") (pintype "passive"))
    )
    (net (code "96") (name "unconnected-(X1H-F-Pad16)") (class "Default")
      (node (ref "X1") (pin "16") (pinfunction "F_16") (pintype "passive"))
    )
    (net (code "97") (name "unconnected-(X1I-F-Pad17)") (class "Default")
      (node (ref "X1") (pin "17") (pinfunction "F_17") (pintype "passive"))
    )
    (net (code "98") (name "unconnected-(X1K-F-Pad19)") (class "Default")
      (node (ref "X1") (pin "19") (pinfunction "F_19") (pintype "passive"))
    )
    (net (code "99") (name "unconnected-(X1M-F-Pad20)") (class "Default")
      (node (ref "X1") (pin "20") (pinfunction "F_20") (pintype "passive"))
    )
    (net (code "100") (name "unconnected-(X1N-F-Pad21)") (class "Default")
      (node (ref "X1") (pin "21") (pinfunction "F_21") (pintype "passive"))
    )
    (net (code "101") (name "unconnected-(X1O-F-Pad22)") (class "Default")
      (node (ref "X1") (pin "22") (pinfunction "F_22") (pintype "passive"))
    )
    (net (code "102") (name "unconnected-(X1P-F-Pad23)") (class "Default")
      (node (ref "X1") (pin "23") (pinfunction "F_23") (pintype "passive"))
    )
    (net (code "103") (name "unconnected-(X1Q-F-Pad24)") (class "Default")
      (node (ref "X1") (pin "24") (pinfunction "F_24") (pintype "passive"))
    )
    (net (code "104") (name "unconnected-(X1R-F-Pad25)") (class "Default")
      (node (ref "X1") (pin "25") (pinfunction "F_25") (pintype "passive"))
    )
    (net (code "105") (name "unconnected-(X1S-F-Pad26)") (class "Default")
      (node (ref "X1") (pin "26") (pinfunction "F_26") (pintype "passive"))
    )
    (net (code "106") (name "unconnected-(X1T-F-Pad27)") (class "Default")
      (node (ref "X1") (pin "27") (pinfunction "F_27") (pintype "passive"))
    )
    (net (code "107") (name "unconnected-(X1U-F-Pad28)") (class "Default")
      (node (ref "X1") (pin "28") (pinfunction "F_28") (pintype "passive"))
    )
    (net (code "108") (name "unconnected-(X1W-F-Pad3)") (class "Default")
      (node (ref "X1") (pin "3") (pinfunction "F_3") (pintype "passive"))
    )
  )
)
